# power2pix_v2.net
KiCad netlist of a schematic drawn in Altium Designer
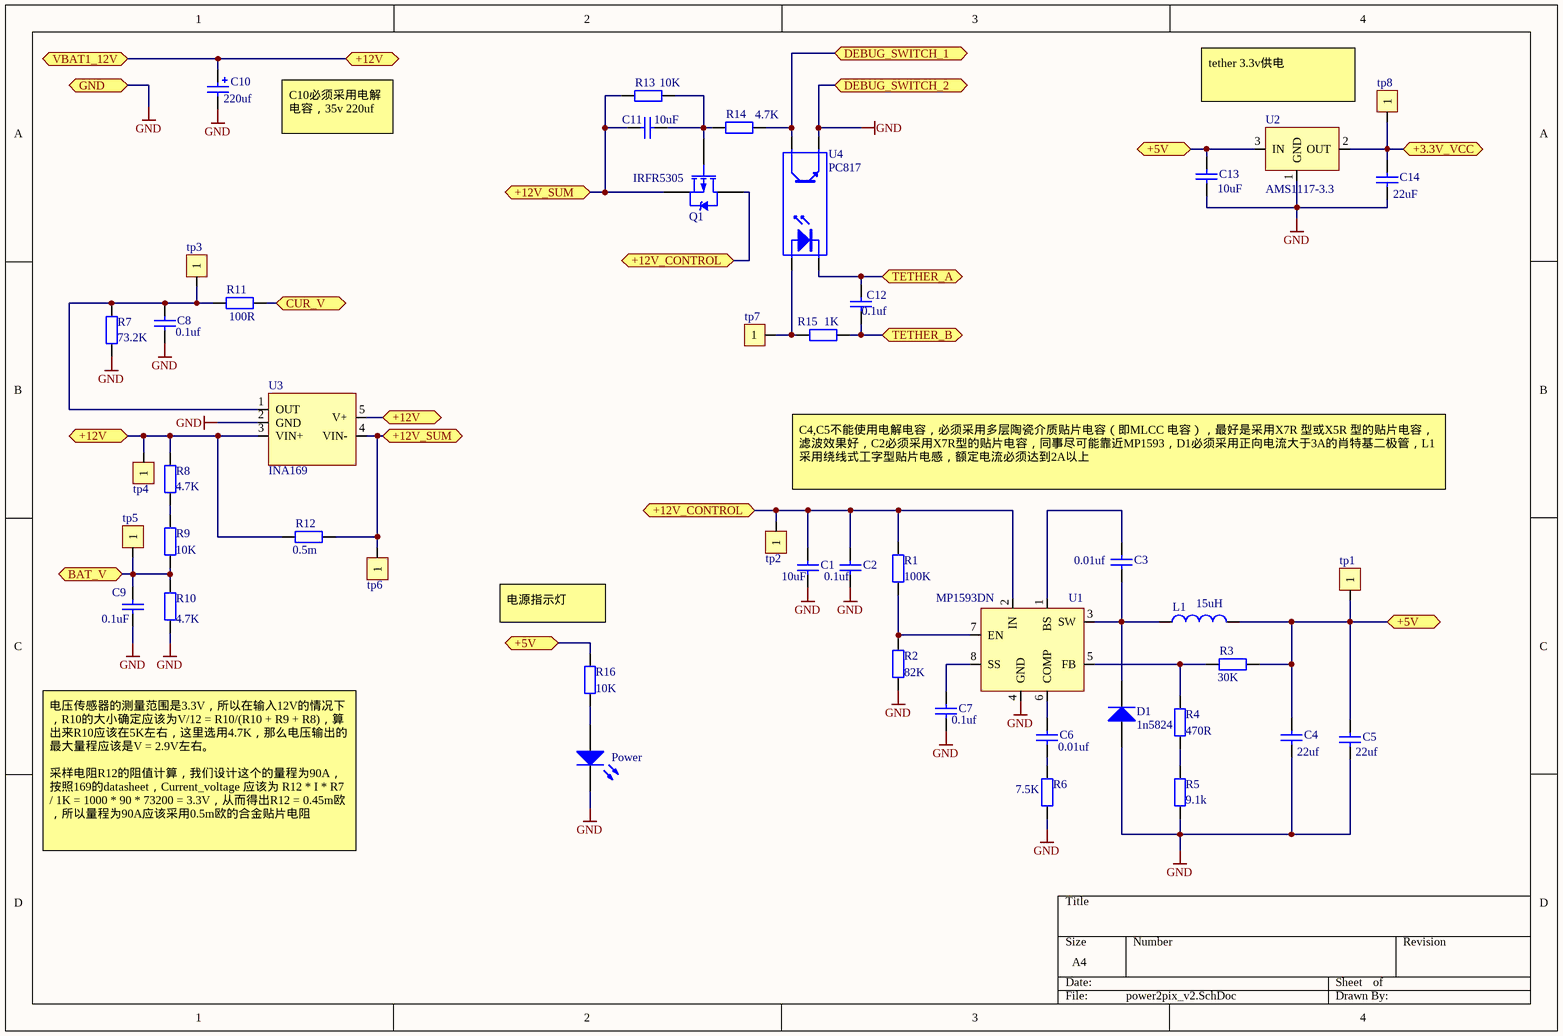
[diagram p0: power2pix_v2.SchDoc]

(export (version "E")
  (design (tool "Eeschema 10.0.6"))
  (components
    (comp (ref "C1")
      (value "10uF")
      (footprint "C1206")
      (description "Capacitor")
      (fields (field (name "Comment") "Cap") (field (name "PUBLISHER") "Altium Limited"))
      (libsource (lib "Miscellaneous Devices") (part "Cap"))
    )
    (comp (ref "C2")
      (value "0.1uf")
      (footprint "6-0805_M")
      (description "Capacitor")
      (fields (field (name "Comment") "Cap") (field (name "PUBLISHER") "Altium Limited"))
      (libsource (lib "Miscellaneous Devices") (part "Cap"))
    )
    (comp (ref "C3")
      (value "0.01uf")
      (footprint "0603")
      (description "Capacitor")
      (fields (field (name "Comment") "Cap") (field (name "PUBLISHER") "Altium Limited"))
      (libsource (lib "Miscellaneous Devices") (part "Cap"))
    )
    (comp (ref "C4")
      (value "22uf")
      (footprint "C1206")
      (description "Capacitor")
      (fields (field (name "Comment") "Cap") (field (name "PUBLISHER") "Altium Limited"))
      (libsource (lib "Miscellaneous Devices") (part "Cap"))
    )
    (comp (ref "C5")
      (value "22uf")
      (footprint "C1206")
      (description "Capacitor")
      (fields (field (name "Comment") "Cap") (field (name "PUBLISHER") "Altium Limited"))
      (libsource (lib "Miscellaneous Devices") (part "Cap"))
    )
    (comp (ref "C6")
      (value "0.01uf")
      (footprint "0603")
      (description "Capacitor")
      (fields (field (name "Comment") "Cap") (field (name "PUBLISHER") "Altium Limited"))
      (libsource (lib "Miscellaneous Devices") (part "Cap"))
    )
    (comp (ref "C7")
      (value "0.1uf")
      (footprint "6-0805_M")
      (description "Capacitor")
      (fields (field (name "Comment") "Cap") (field (name "PUBLISHER") "Altium Limited"))
      (libsource (lib "Miscellaneous Devices") (part "Cap"))
    )
    (comp (ref "C8")
      (value "0.1uf")
      (footprint "6-0805_M")
      (description "Capacitor")
      (fields (field (name "Comment") "Cap") (field (name "PUBLISHER") "Altium Limited"))
      (libsource (lib "Miscellaneous Devices") (part "Cap"))
    )
    (comp (ref "C9")
      (value "0.1uF")
      (footprint "6-0805_M")
      (description "Capacitor")
      (fields (field (name "Comment") "Cap") (field (name "PUBLISHER") "Altium Limited"))
      (libsource (lib "Miscellaneous Devices") (part "Cap"))
    )
    (comp (ref "C10")
      (value "220uf")
      (footprint "220UF-35V")
      (description "Polarized Capacitor (Axial)")
      (fields (field (name "Comment") "Cap Pol2") (field (name "PUBLISHER") "Altium Limited"))
      (libsource (lib "Miscellaneous Devices") (part "Cap Pol2"))
    )
    (comp (ref "C11")
      (value "10uF")
      (footprint "C1206")
      (description "Capacitor")
      (fields (field (name "Comment") "Cap") (field (name "PUBLISHER") "Altium Limited"))
      (libsource (lib "Miscellaneous Devices") (part "Cap"))
    )
    (comp (ref "C12")
      (value "0.1uf")
      (footprint "6-0805_M")
      (description "Capacitor")
      (fields (field (name "Comment") "Cap") (field (name "PUBLISHER") "Altium Limited"))
      (libsource (lib "Miscellaneous Devices") (part "Cap"))
    )
    (comp (ref "C13")
      (value "10uF")
      (footprint "1206")
      (description "Capacitor")
      (fields (field (name "Comment") "Cap") (field (name "PUBLISHER") "Altium Limited"))
      (libsource (lib "Miscellaneous Devices") (part "Cap"))
    )
    (comp (ref "C14")
      (value "22uF")
      (footprint "my0603")
      (description "Capacitor")
      (fields (field (name "Comment") "Cap") (field (name "PUBLISHER") "Altium Limited"))
      (libsource (lib "Miscellaneous Devices") (part "Cap"))
    )
    (comp (ref "D1")
      (value "1n5824")
      (footprint "1N5824")
      (description "Default Diode")
      (fields (field (name "PUBLISHER") "Altium Limited"))
      (libsource (lib "Miscellaneous Devices") (part "Diode"))
    )
    (comp (ref "L1")
      (value "15uH")
      (footprint "0630")
      (description "Inductor")
      (fields (field (name "PUBLISHER") "Altium Limited"))
      (libsource (lib "Miscellaneous Devices") (part "Inductor"))
    )
    (comp (ref "Power")
      (value "LED0")
      (footprint "6-0805_L")
      (description "Typical INFRARED GaAs LED")
      (fields (field (name "PUBLISHER") "Altium Limited"))
      (libsource (lib "Miscellaneous Devices") (part "LED0"))
    )
    (comp (ref "Q1")
      (value "IRFR5305")
      (footprint "TO-252AA")
      (description "P-Channel Power MOSFET")
      (fields (field (name "PUBLISHER") "Altium Limited"))
      (libsource (lib "Miscellaneous Devices") (part "PMOS-2"))
    )
    (comp (ref "R1")
      (value "100K")
      (footprint "6-0805_M")
      (description "Resistor")
      (fields (field (name "Comment") "Res2") (field (name "PUBLISHER") "Altium Limited"))
      (libsource (lib "Miscellaneous Devices") (part "Res2"))
    )
    (comp (ref "R2")
      (value "82K")
      (footprint "6-0805_M")
      (description "Resistor")
      (fields (field (name "Comment") "Res2") (field (name "PUBLISHER") "Altium Limited"))
      (libsource (lib "Miscellaneous Devices") (part "Res2"))
    )
    (comp (ref "R3")
      (value "30K")
      (footprint "6-0805_M")
      (description "Resistor")
      (fields (field (name "Comment") "Res2") (field (name "PUBLISHER") "Altium Limited"))
      (libsource (lib "") (part "Res2_2"))
    )
    (comp (ref "R4")
      (value "470R")
      (footprint "6-0805_M")
      (description "Resistor")
      (fields (field (name "Comment") "Res2") (field (name "PUBLISHER") "Altium Limited"))
      (libsource (lib "Miscellaneous Devices") (part "Res2"))
    )
    (comp (ref "R5")
      (value "9.1k")
      (footprint "6-0805_M")
      (description "Resistor")
      (fields (field (name "Comment") "Res2") (field (name "PUBLISHER") "Altium Limited"))
      (libsource (lib "Miscellaneous Devices") (part "Res2"))
    )
    (comp (ref "R6")
      (value "7.5K")
      (footprint "6-0805_M")
      (description "Resistor")
      (fields (field (name "Comment") "Res2") (field (name "PUBLISHER") "Altium Limited"))
      (libsource (lib "Miscellaneous Devices") (part "Res2"))
    )
    (comp (ref "R7")
      (value "73.2K")
      (footprint "my0603")
      (description "Resistor")
      (fields (field (name "Comment") "Res2") (field (name "PUBLISHER") "Altium Limited"))
      (libsource (lib "Miscellaneous Devices") (part "Res2"))
    )
    (comp (ref "R8")
      (value "4.7K")
      (footprint "6-0805_M")
      (description "Resistor")
      (fields (field (name "Comment") "Res2") (field (name "PUBLISHER") "Altium Limited"))
      (libsource (lib "Miscellaneous Devices") (part "Res2"))
    )
    (comp (ref "R9")
      (value "10K")
      (footprint "6-0805_M")
      (description "Resistor")
      (fields (field (name "Comment") "Res2") (field (name "PUBLISHER") "Altium Limited"))
      (libsource (lib "Miscellaneous Devices") (part "Res2"))
    )
    (comp (ref "R10")
      (value "4.7K")
      (footprint "6-0805_M")
      (description "Resistor")
      (fields (field (name "Comment") "Res2") (field (name "PUBLISHER") "Altium Limited"))
      (libsource (lib "Miscellaneous Devices") (part "Res2"))
    )
    (comp (ref "R11")
      (value "100R")
      (footprint "6-0805_M")
      (description "Resistor")
      (fields (field (name "Comment") "Res2") (field (name "PUBLISHER") "Altium Limited"))
      (libsource (lib "") (part "Res2_1"))
    )
    (comp (ref "R12")
      (value "0.5m")
      (footprint "2512")
      (description "Resistor")
      (fields (field (name "Comment") "Res2") (field (name "PUBLISHER") "Altium Limited"))
      (libsource (lib "") (part "Res2_1"))
    )
    (comp (ref "R13")
      (value "10K")
      (footprint "6-0805_M")
      (description "Resistor")
      (fields (field (name "Comment") "Res2") (field (name "PUBLISHER") "Altium Limited"))
      (libsource (lib "") (part "Res2_1"))
    )
    (comp (ref "R14")
      (value "4.7K")
      (footprint "6-0805_M")
      (description "Resistor")
      (fields (field (name "Comment") "Res2") (field (name "PUBLISHER") "Altium Limited"))
      (libsource (lib "") (part "Res2_1"))
    )
    (comp (ref "R15")
      (value "1K")
      (footprint "6-0805_M")
      (description "Resistor")
      (fields (field (name "Comment") "Res2") (field (name "PUBLISHER") "Altium Limited"))
      (libsource (lib "") (part "Res2_1"))
    )
    (comp (ref "R16")
      (value "10K")
      (footprint "6-0805_L")
      (description "Resistor")
      (fields (field (name "Comment") "Res2") (field (name "PUBLISHER") "Altium Limited"))
      (libsource (lib "Miscellaneous Devices") (part "Res2"))
    )
    (comp (ref "tp1") (value "tp") (footprint "testpoint") (libsource (lib "") (part "tp_1")))
    (comp (ref "tp2") (value "tp") (footprint "testpoint") (libsource (lib "power2pix_sch_lib") (part "tp")))
    (comp (ref "tp3") (value "tp") (footprint "testpoint") (libsource (lib "") (part "tp_1")))
    (comp (ref "tp4") (value "tp") (footprint "testpoint") (libsource (lib "power2pix_sch_lib") (part "tp")))
    (comp (ref "tp5") (value "tp") (footprint "testpoint") (libsource (lib "") (part "tp_1")))
    (comp (ref "tp6") (value "tp") (footprint "testpoint") (libsource (lib "power2pix_sch_lib") (part "tp")))
    (comp (ref "tp7") (value "tp") (footprint "testpoint") (libsource (lib "") (part "tp_2")))
    (comp (ref "tp8") (value "tp") (footprint "testpoint") (libsource (lib "") (part "tp_1")))
    (comp (ref "U1")
      (value "MP1593DN")
      (footprint "SO8_M")
      (libsource (lib "power2pix_sch_lib") (part "MP1593DN"))
    )
    (comp (ref "U2")
      (value "AMS1117-3.3")
      (footprint "SOT223_M")
      (libsource (lib "buoys_sch_lib") (part "AMS1117-3.3"))
    )
    (comp (ref "U3")
      (value "INA169")
      (footprint "SOT23-5")
      (libsource (lib "power2pix_sch_lib") (part "INA169"))
    )
    (comp (ref "U4")
      (value "PC817")
      (footprint "DIP-4")
      (description "4-Pin Phototransistor Optocoupler")
      (fields (field (name "PUBLISHER") "Altium Limited"))
      (libsource (lib "Miscellaneous Devices") (part "Optoisolator1"))
    )
  )
  (nets
    (net (code "1") (name "/+3.3V_VCC") (class "Default")
      (node (ref "C14") (pin "2") (pinfunction "2_2") (pintype "passive"))
      (node (ref "U2") (pin "2") (pinfunction "OUT_2") (pintype "passive"))
      (node (ref "tp8") (pin "1") (pinfunction "1_1") (pintype "passive"))
    )
    (net (code "2") (name "/+5V") (class "Default")
      (node (ref "C13") (pin "2") (pinfunction "2_2") (pintype "passive"))
      (node (ref "C4") (pin "2") (pinfunction "2_2") (pintype "passive"))
      (node (ref "C5") (pin "2") (pinfunction "2_2") (pintype "passive"))
      (node (ref "L1") (pin "2") (pinfunction "2_2") (pintype "passive"))
      (node (ref "R16") (pin "2") (pinfunction "2_2") (pintype "passive"))
      (node (ref "R3") (pin "1") (pinfunction "1_1") (pintype "passive"))
      (node (ref "U2") (pin "3") (pinfunction "IN_3") (pintype "passive"))
      (node (ref "tp1") (pin "1") (pinfunction "1_1") (pintype "passive"))
    )
    (net (code "3") (name "/+12V") (class "Default")
      (node (ref "C10") (pin "1") (pinfunction "1_1") (pintype "passive"))
      (node (ref "R12") (pin "1") (pinfunction "1_1") (pintype "passive"))
      (node (ref "R8") (pin "2") (pinfunction "2_2") (pintype "passive"))
      (node (ref "U3") (pin "3") (pinfunction "VIN+_3") (pintype "passive"))
      (node (ref "U3") (pin "5") (pinfunction "V+_5") (pintype "passive"))
      (node (ref "tp4") (pin "1") (pinfunction "1_1") (pintype "passive"))
    )
    (net (code "4") (name "/+12V_CONTROL") (class "Default")
      (node (ref "C1") (pin "2") (pinfunction "2_2") (pintype "passive"))
      (node (ref "C2") (pin "2") (pinfunction "2_2") (pintype "passive"))
      (node (ref "Q1") (pin "4") (pinfunction "D_4") (pintype "passive"))
      (node (ref "R1") (pin "2") (pinfunction "2_2") (pintype "passive"))
      (node (ref "U1") (pin "2") (pinfunction "IN_2") (pintype "passive"))
      (node (ref "tp2") (pin "1") (pinfunction "1_1") (pintype "passive"))
    )
    (net (code "5") (name "/+12V_SUM") (class "Default")
      (node (ref "C11") (pin "1") (pinfunction "1_1") (pintype "passive"))
      (node (ref "Q1") (pin "3") (pinfunction "S_3") (pintype "passive"))
      (node (ref "R12") (pin "2") (pinfunction "2_2") (pintype "passive"))
      (node (ref "R13") (pin "1") (pinfunction "1_1") (pintype "passive"))
      (node (ref "U3") (pin "4") (pinfunction "VIN-_4") (pintype "passive"))
      (node (ref "tp6") (pin "1") (pinfunction "1_1") (pintype "passive"))
    )
    (net (code "6") (name "/BAT_V") (class "Default")
      (node (ref "C9") (pin "2") (pinfunction "2_2") (pintype "passive"))
      (node (ref "R10") (pin "2") (pinfunction "2_2") (pintype "passive"))
      (node (ref "R9") (pin "1") (pinfunction "1_1") (pintype "passive"))
      (node (ref "tp5") (pin "1") (pinfunction "1_1") (pintype "passive"))
    )
    (net (code "7") (name "/CUR_V") (class "Default")
      (node (ref "R11") (pin "2") (pinfunction "2_2") (pintype "passive"))
    )
    (net (code "8") (name "/DEBUG_SWITCH_1") (class "Default")
      (node (ref "R14") (pin "2") (pinfunction "2_2") (pintype "passive"))
      (node (ref "U4") (pin "4") (pinfunction "C_4") (pintype "passive"))
    )
    (net (code "9") (name "/TETHER_A") (class "Default")
      (node (ref "C12") (pin "2") (pinfunction "2_2") (pintype "passive"))
      (node (ref "U4") (pin "2") (pinfunction "K_2") (pintype "passive"))
    )
    (net (code "10") (name "/TETHER_B") (class "Default")
      (node (ref "C12") (pin "1") (pinfunction "1_1") (pintype "passive"))
      (node (ref "R15") (pin "2") (pinfunction "2_2") (pintype "passive"))
    )
    (net (code "11") (name "GND") (class "Default")
      (node (ref "C1") (pin "1") (pinfunction "1_1") (pintype "passive"))
      (node (ref "C10") (pin "2") (pinfunction "2_2") (pintype "passive"))
      (node (ref "C13") (pin "1") (pinfunction "1_1") (pintype "passive"))
      (node (ref "C14") (pin "1") (pinfunction "1_1") (pintype "passive"))
      (node (ref "C2") (pin "1") (pinfunction "1_1") (pintype "passive"))
      (node (ref "C4") (pin "1") (pinfunction "1_1") (pintype "passive"))
      (node (ref "C5") (pin "1") (pinfunction "1_1") (pintype "passive"))
      (node (ref "C7") (pin "1") (pinfunction "1_1") (pintype "passive"))
      (node (ref "C8") (pin "1") (pinfunction "1_1") (pintype "passive"))
      (node (ref "C9") (pin "1") (pinfunction "1_1") (pintype "passive"))
      (node (ref "D1") (pin "1") (pinfunction "A_1") (pintype "passive"))
      (node (ref "Power") (pin "2") (pinfunction "K_2") (pintype "passive"))
      (node (ref "R10") (pin "1") (pinfunction "1_1") (pintype "passive"))
      (node (ref "R2") (pin "1") (pinfunction "1_1") (pintype "passive"))
      (node (ref "R5") (pin "1") (pinfunction "1_1") (pintype "passive"))
      (node (ref "R6") (pin "1") (pinfunction "1_1") (pintype "passive"))
      (node (ref "R7") (pin "1") (pinfunction "1_1") (pintype "passive"))
      (node (ref "U1") (pin "4") (pinfunction "GND_4") (pintype "passive"))
      (node (ref "U2") (pin "1") (pinfunction "GND_1") (pintype "passive"))
      (node (ref "U3") (pin "2") (pinfunction "GND_2") (pintype "passive"))
      (node (ref "U4") (pin "3") (pinfunction "E_3") (pintype "passive"))
    )
    (net (code "12") (name "Net-(C6-Pad1)") (class "Default")
      (node (ref "C6") (pin "1") (pinfunction "1_1") (pintype "passive"))
      (node (ref "R6") (pin "2") (pinfunction "2_2") (pintype "passive"))
    )
    (net (code "13") (name "Net-(D1-K)") (class "Default")
      (node (ref "C3") (pin "1") (pinfunction "1_1") (pintype "passive"))
      (node (ref "D1") (pin "2") (pinfunction "K_2") (pintype "passive"))
      (node (ref "L1") (pin "1") (pinfunction "1_1") (pintype "passive"))
      (node (ref "U1") (pin "3") (pinfunction "SW_3") (pintype "passive"))
    )
    (net (code "14") (name "Net-(Power-A)") (class "Default")
      (node (ref "Power") (pin "1") (pinfunction "A_1") (pintype "passive"))
      (node (ref "R16") (pin "1") (pinfunction "1_1") (pintype "passive"))
    )
    (net (code "15") (name "Net-(Q1-G)") (class "Default")
      (node (ref "C11") (pin "2") (pinfunction "2_2") (pintype "passive"))
      (node (ref "Q1") (pin "1") (pinfunction "G_1") (pintype "passive"))
      (node (ref "R13") (pin "2") (pinfunction "2_2") (pintype "passive"))
      (node (ref "R14") (pin "1") (pinfunction "1_1") (pintype "passive"))
    )
    (net (code "16") (name "Net-(R4-Pad1)") (class "Default")
      (node (ref "R4") (pin "1") (pinfunction "1_1") (pintype "passive"))
      (node (ref "R5") (pin "2") (pinfunction "2_2") (pintype "passive"))
    )
    (net (code "17") (name "Net-(R8-Pad1)") (class "Default")
      (node (ref "R8") (pin "1") (pinfunction "1_1") (pintype "passive"))
      (node (ref "R9") (pin "2") (pinfunction "2_2") (pintype "passive"))
    )
    (net (code "18") (name "Net-(U1-BS)") (class "Default")
      (node (ref "C3") (pin "2") (pinfunction "2_2") (pintype "passive"))
      (node (ref "U1") (pin "1") (pinfunction "BS_1") (pintype "passive"))
    )
    (net (code "19") (name "Net-(U1-COMP)") (class "Default")
      (node (ref "C6") (pin "2") (pinfunction "2_2") (pintype "passive"))
      (node (ref "U1") (pin "6") (pinfunction "COMP_6") (pintype "passive"))
    )
    (net (code "20") (name "Net-(U1-EN)") (class "Default")
      (node (ref "R1") (pin "1") (pinfunction "1_1") (pintype "passive"))
      (node (ref "R2") (pin "2") (pinfunction "2_2") (pintype "passive"))
      (node (ref "U1") (pin "7") (pinfunction "EN_7") (pintype "passive"))
    )
    (net (code "21") (name "Net-(U1-FB)") (class "Default")
      (node (ref "R3") (pin "2") (pinfunction "2_2") (pintype "passive"))
      (node (ref "R4") (pin "2") (pinfunction "2_2") (pintype "passive"))
      (node (ref "U1") (pin "5") (pinfunction "FB_5") (pintype "passive"))
    )
    (net (code "22") (name "Net-(U1-SS)") (class "Default")
      (node (ref "C7") (pin "2") (pinfunction "2_2") (pintype "passive"))
      (node (ref "U1") (pin "8") (pinfunction "SS_8") (pintype "passive"))
    )
    (net (code "23") (name "Net-(U3-OUT)") (class "Default")
      (node (ref "C8") (pin "2") (pinfunction "2_2") (pintype "passive"))
      (node (ref "R11") (pin "1") (pinfunction "1_1") (pintype "passive"))
      (node (ref "R7") (pin "2") (pinfunction "2_2") (pintype "passive"))
      (node (ref "U3") (pin "1") (pinfunction "OUT_1") (pintype "passive"))
      (node (ref "tp3") (pin "1") (pinfunction "1_1") (pintype "passive"))
    )
    (net (code "24") (name "Net-(U4-A)") (class "Default")
      (node (ref "R15") (pin "1") (pinfunction "1_1") (pintype "passive"))
      (node (ref "U4") (pin "1") (pinfunction "A_1") (pintype "passive"))
      (node (ref "tp7") (pin "1") (pinfunction "1_1") (pintype "passive"))
    )
  )
)
